# Dual_linear_VCA_chip_v3_0_-_external_tri.net
KiCad netlist of a schematic drawn in EAGLE
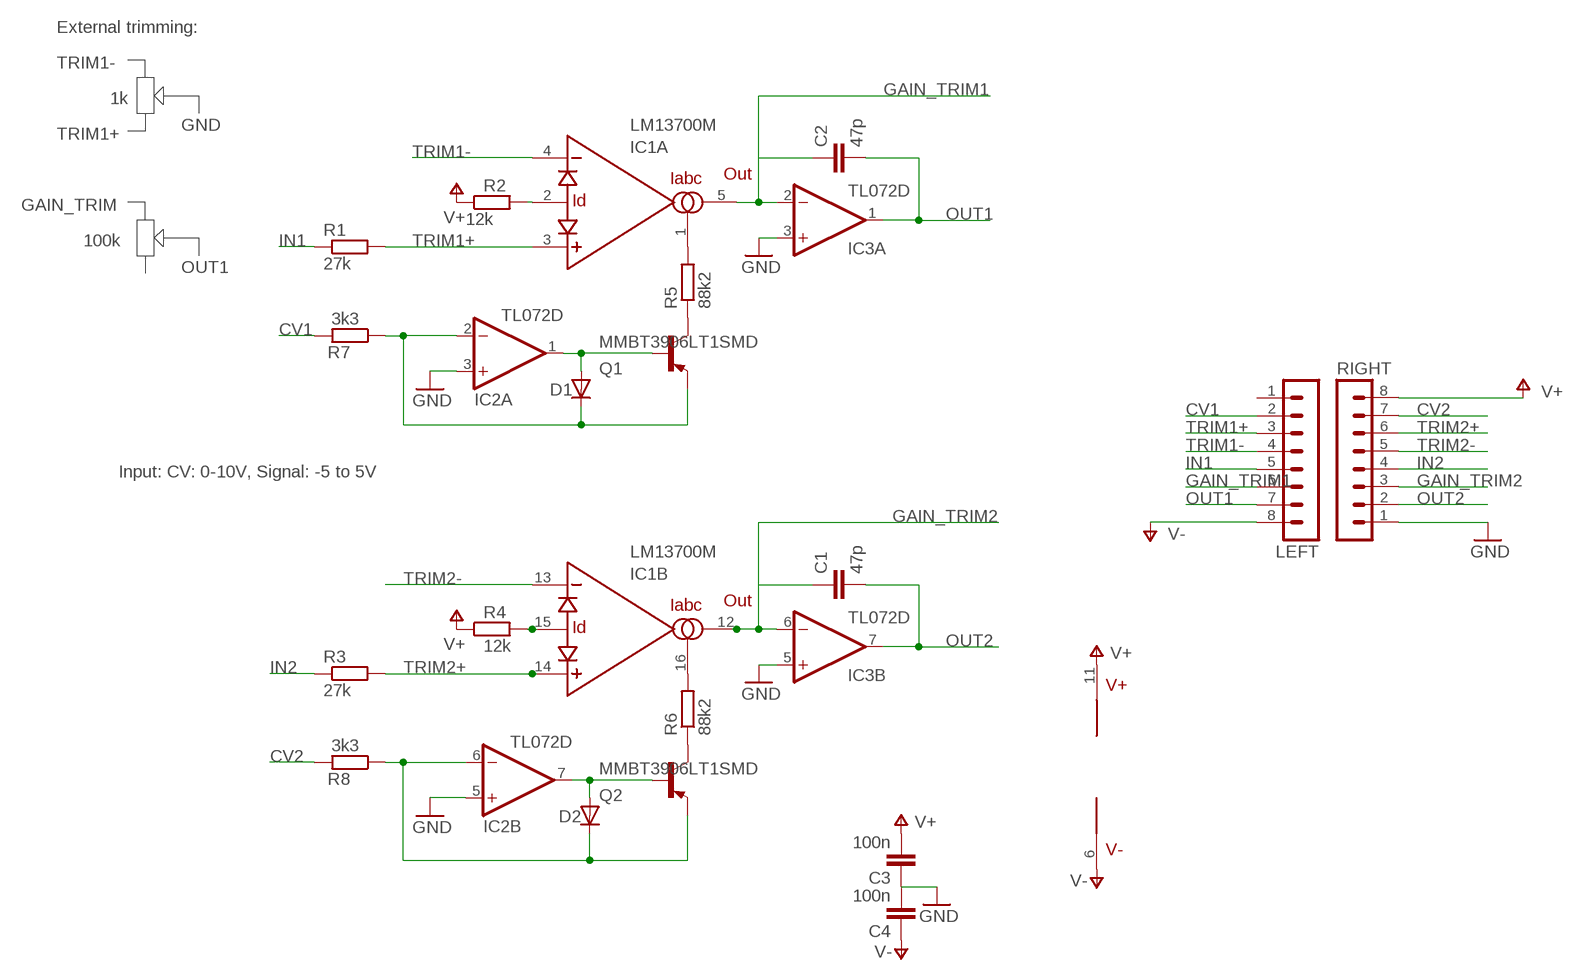
[diagram p0: schematic, sheet 1]

(export (version "E")
  (design (tool "Eeschema 10.0.6"))
  (components
    (comp (ref "C1")
      (value "47p")
      (footprint "eagle-import:C0805")
      (libsource (lib "eagle-import") (part "C-EUC0805"))
    )
    (comp (ref "C2")
      (value "47p")
      (footprint "eagle-import:C0805")
      (libsource (lib "eagle-import") (part "C-EUC0805"))
    )
    (comp (ref "C3")
      (value "100n")
      (footprint "eagle-import:C0805")
      (libsource (lib "eagle-import") (part "C-EUC0805"))
    )
    (comp (ref "C4")
      (value "100n")
      (footprint "eagle-import:C0805")
      (libsource (lib "eagle-import") (part "C-EUC0805"))
    )
    (comp (ref "D1")
      (value "DIODE-SOD80C")
      (footprint "eagle-import:SOD80C")
      (libsource (lib "eagle-import") (part "DIODE-SOD80C"))
    )
    (comp (ref "D2")
      (value "DIODE-SOD80C")
      (footprint "eagle-import:SOD80C")
      (libsource (lib "eagle-import") (part "DIODE-SOD80C"))
    )
    (comp (ref "IC1")
      (value "LM13700M")
      (footprint "eagle-import:SO16")
      (libsource (lib "eagle-import") (part "LM13700M"))
    )
    (comp (ref "IC2")
      (value "TL072D")
      (footprint "eagle-import:SO08")
      (libsource (lib "eagle-import") (part "TL072D"))
    )
    (comp (ref "IC3")
      (value "TL072D")
      (footprint "eagle-import:SO08")
      (libsource (lib "eagle-import") (part "TL072D"))
    )
    (comp (ref "LEFT")
      (value "MA08-1JC")
      (footprint "eagle-import:MA08-1J")
      (libsource (lib "eagle-import") (part "MA08-1JC"))
    )
    (comp (ref "Q1")
      (value "MMBT3906LT1SMD")
      (footprint "eagle-import:SOT23-BEC")
      (libsource (lib "eagle-import") (part "MMBT3906SMDLT1"))
    )
    (comp (ref "Q2")
      (value "MMBT3906LT1SMD")
      (footprint "eagle-import:SOT23-BEC")
      (libsource (lib "eagle-import") (part "MMBT3906SMDLT1"))
    )
    (comp (ref "R1")
      (value "27k")
      (footprint "eagle-import:R0805")
      (libsource (lib "eagle-import") (part "R-EU_R0805"))
    )
    (comp (ref "R2")
      (value "12k")
      (footprint "eagle-import:R0805")
      (libsource (lib "eagle-import") (part "R-EU_R0805"))
    )
    (comp (ref "R3")
      (value "27k")
      (footprint "eagle-import:R0805")
      (libsource (lib "eagle-import") (part "R-EU_R0805"))
    )
    (comp (ref "R4")
      (value "12k")
      (footprint "eagle-import:R0805")
      (libsource (lib "eagle-import") (part "R-EU_R0805"))
    )
    (comp (ref "R5")
      (value "88k2")
      (footprint "eagle-import:R0805")
      (libsource (lib "eagle-import") (part "R-EU_R0805"))
    )
    (comp (ref "R6")
      (value "88k2")
      (footprint "eagle-import:R0805")
      (libsource (lib "eagle-import") (part "R-EU_R0805"))
    )
    (comp (ref "R7")
      (value "3k3")
      (footprint "eagle-import:R0805")
      (libsource (lib "eagle-import") (part "R-EU_R0805"))
    )
    (comp (ref "R8")
      (value "3k3")
      (footprint "eagle-import:R0805")
      (libsource (lib "eagle-import") (part "R-EU_R0805"))
    )
    (comp (ref "RIGHT")
      (value "MA08-1JC")
      (footprint "eagle-import:MA08-1J")
      (libsource (lib "eagle-import") (part "MA08-1JC"))
    )
  )
  (nets
    (net (code "1") (name "/CV1") (class "Default")
      (node (ref "LEFT") (pin "2") (pinfunction "2_2") (pintype "passive"))
      (node (ref "R7") (pin "2") (pinfunction "2_2") (pintype "passive"))
    )
    (net (code "2") (name "/CV2") (class "Default")
      (node (ref "R8") (pin "2") (pinfunction "2_2") (pintype "passive"))
      (node (ref "RIGHT") (pin "7") (pinfunction "7_7") (pintype "passive"))
    )
    (net (code "3") (name "/GAIN_TRIM1") (class "Default")
      (node (ref "C2") (pin "1") (pinfunction "1_1") (pintype "passive"))
      (node (ref "IC1") (pin "5") (pinfunction "OUT_5") (pintype "bidirectional"))
      (node (ref "IC3") (pin "2") (pinfunction "-IN_2") (pintype "input"))
      (node (ref "LEFT") (pin "6") (pinfunction "6_6") (pintype "passive"))
    )
    (net (code "4") (name "/GAIN_TRIM2") (class "Default")
      (node (ref "C1") (pin "1") (pinfunction "1_1") (pintype "passive"))
      (node (ref "IC1") (pin "12") (pinfunction "OUT_12") (pintype "bidirectional"))
      (node (ref "IC3") (pin "6") (pinfunction "-IN_6") (pintype "input"))
      (node (ref "RIGHT") (pin "3") (pinfunction "3_3") (pintype "passive"))
    )
    (net (code "5") (name "/IN1") (class "Default")
      (node (ref "LEFT") (pin "5") (pinfunction "5_5") (pintype "passive"))
      (node (ref "R1") (pin "1") (pinfunction "1_1") (pintype "passive"))
    )
    (net (code "6") (name "/IN2") (class "Default")
      (node (ref "R3") (pin "1") (pinfunction "1_1") (pintype "passive"))
      (node (ref "RIGHT") (pin "4") (pinfunction "4_4") (pintype "passive"))
    )
    (net (code "7") (name "/OUT1") (class "Default")
      (node (ref "C2") (pin "2") (pinfunction "2_2") (pintype "passive"))
      (node (ref "IC3") (pin "1") (pinfunction "OUT_1") (pintype "output"))
      (node (ref "LEFT") (pin "7") (pinfunction "7_7") (pintype "passive"))
    )
    (net (code "8") (name "/OUT2") (class "Default")
      (node (ref "C1") (pin "2") (pinfunction "2_2") (pintype "passive"))
      (node (ref "IC3") (pin "7") (pinfunction "OUT_7") (pintype "output"))
      (node (ref "RIGHT") (pin "2") (pinfunction "2_2") (pintype "passive"))
    )
    (net (code "9") (name "/TRIM1+") (class "Default")
      (node (ref "IC1") (pin "3") (pinfunction "+IN_3") (pintype "bidirectional"))
      (node (ref "LEFT") (pin "3") (pinfunction "3_3") (pintype "passive"))
      (node (ref "R1") (pin "2") (pinfunction "2_2") (pintype "passive"))
    )
    (net (code "10") (name "/TRIM1-") (class "Default")
      (node (ref "IC1") (pin "4") (pinfunction "-IN_4") (pintype "bidirectional"))
      (node (ref "LEFT") (pin "4") (pinfunction "4_4") (pintype "passive"))
    )
    (net (code "11") (name "/TRIM2+") (class "Default")
      (node (ref "IC1") (pin "14") (pinfunction "+IN_14") (pintype "bidirectional"))
      (node (ref "R3") (pin "2") (pinfunction "2_2") (pintype "passive"))
      (node (ref "RIGHT") (pin "6") (pinfunction "6_6") (pintype "passive"))
    )
    (net (code "12") (name "/TRIM2-") (class "Default")
      (node (ref "IC1") (pin "13") (pinfunction "-IN_13") (pintype "bidirectional"))
      (node (ref "RIGHT") (pin "5") (pinfunction "5_5") (pintype "passive"))
    )
    (net (code "13") (name "GND") (class "Default")
      (node (ref "C3") (pin "1") (pinfunction "1_1") (pintype "passive"))
      (node (ref "C4") (pin "2") (pinfunction "2_2") (pintype "passive"))
      (node (ref "IC2") (pin "3") (pinfunction "+IN_3") (pintype "input"))
      (node (ref "IC2") (pin "5") (pinfunction "+IN_5") (pintype "input"))
      (node (ref "IC3") (pin "3") (pinfunction "+IN_3") (pintype "input"))
      (node (ref "IC3") (pin "5") (pinfunction "+IN_5") (pintype "input"))
      (node (ref "RIGHT") (pin "1") (pinfunction "1_1") (pintype "passive"))
    )
    (net (code "14") (name "Net-(IC1A-IABC)") (class "Default")
      (node (ref "IC1") (pin "1") (pinfunction "IABC_1") (pintype "bidirectional"))
      (node (ref "R5") (pin "2") (pinfunction "2_2") (pintype "passive"))
    )
    (net (code "15") (name "Net-(IC1A-ID)") (class "Default")
      (node (ref "IC1") (pin "2") (pinfunction "ID_2") (pintype "bidirectional"))
      (node (ref "R2") (pin "2") (pinfunction "2_2") (pintype "passive"))
    )
    (net (code "16") (name "Net-(IC1B-IABC)") (class "Default")
      (node (ref "IC1") (pin "16") (pinfunction "IABC_16") (pintype "bidirectional"))
      (node (ref "R6") (pin "2") (pinfunction "2_2") (pintype "passive"))
    )
    (net (code "17") (name "Net-(IC1B-ID)") (class "Default")
      (node (ref "IC1") (pin "15") (pinfunction "ID_15") (pintype "bidirectional"))
      (node (ref "R4") (pin "2") (pinfunction "2_2") (pintype "passive"))
    )
    (net (code "18") (name "Net-(IC2A--IN)") (class "Default")
      (node (ref "D1") (pin "C") (pinfunction "C_C") (pintype "passive"))
      (node (ref "IC2") (pin "2") (pinfunction "-IN_2") (pintype "input"))
      (node (ref "Q1") (pin "E") (pinfunction "E_E") (pintype "passive"))
      (node (ref "R7") (pin "1") (pinfunction "1_1") (pintype "passive"))
    )
    (net (code "19") (name "Net-(IC2A-OUT)") (class "Default")
      (node (ref "D1") (pin "A") (pinfunction "A_A") (pintype "passive"))
      (node (ref "IC2") (pin "1") (pinfunction "OUT_1") (pintype "output"))
      (node (ref "Q1") (pin "B") (pinfunction "B_B") (pintype "passive"))
    )
    (net (code "20") (name "Net-(IC2B--IN)") (class "Default")
      (node (ref "D2") (pin "C") (pinfunction "C_C") (pintype "passive"))
      (node (ref "IC2") (pin "6") (pinfunction "-IN_6") (pintype "input"))
      (node (ref "Q2") (pin "E") (pinfunction "E_E") (pintype "passive"))
      (node (ref "R8") (pin "1") (pinfunction "1_1") (pintype "passive"))
    )
    (net (code "21") (name "Net-(IC2B-OUT)") (class "Default")
      (node (ref "D2") (pin "A") (pinfunction "A_A") (pintype "passive"))
      (node (ref "IC2") (pin "7") (pinfunction "OUT_7") (pintype "output"))
      (node (ref "Q2") (pin "B") (pinfunction "B_B") (pintype "passive"))
    )
    (net (code "22") (name "Net-(Q1-PadC)") (class "Default")
      (node (ref "Q1") (pin "C") (pinfunction "C_C") (pintype "passive"))
      (node (ref "R5") (pin "1") (pinfunction "1_1") (pintype "passive"))
    )
    (net (code "23") (name "Net-(Q2-PadC)") (class "Default")
      (node (ref "Q2") (pin "C") (pinfunction "C_C") (pintype "passive"))
      (node (ref "R6") (pin "1") (pinfunction "1_1") (pintype "passive"))
    )
    (net (code "24") (name "V+") (class "Default")
      (node (ref "C3") (pin "2") (pinfunction "2_2") (pintype "passive"))
      (node (ref "IC1") (pin "11") (pinfunction "V+_11") (pintype "bidirectional"))
      (node (ref "R2") (pin "1") (pinfunction "1_1") (pintype "passive"))
      (node (ref "R4") (pin "1") (pinfunction "1_1") (pintype "passive"))
      (node (ref "RIGHT") (pin "8") (pinfunction "8_8") (pintype "passive"))
    )
    (net (code "25") (name "V-") (class "Default")
      (node (ref "C4") (pin "1") (pinfunction "1_1") (pintype "passive"))
      (node (ref "IC1") (pin "6") (pinfunction "V-_6") (pintype "bidirectional"))
      (node (ref "LEFT") (pin "8") (pinfunction "8_8") (pintype "passive"))
    )
    (net (code "26") (name "unconnected-(LEFT-Pad1)") (class "Default")
      (node (ref "LEFT") (pin "1") (pinfunction "1_1") (pintype "passive"))
    )
  )
)
